# Rov3_-_zasilanie_silniki_v4.net
KiCad netlist of a schematic drawn in EAGLE
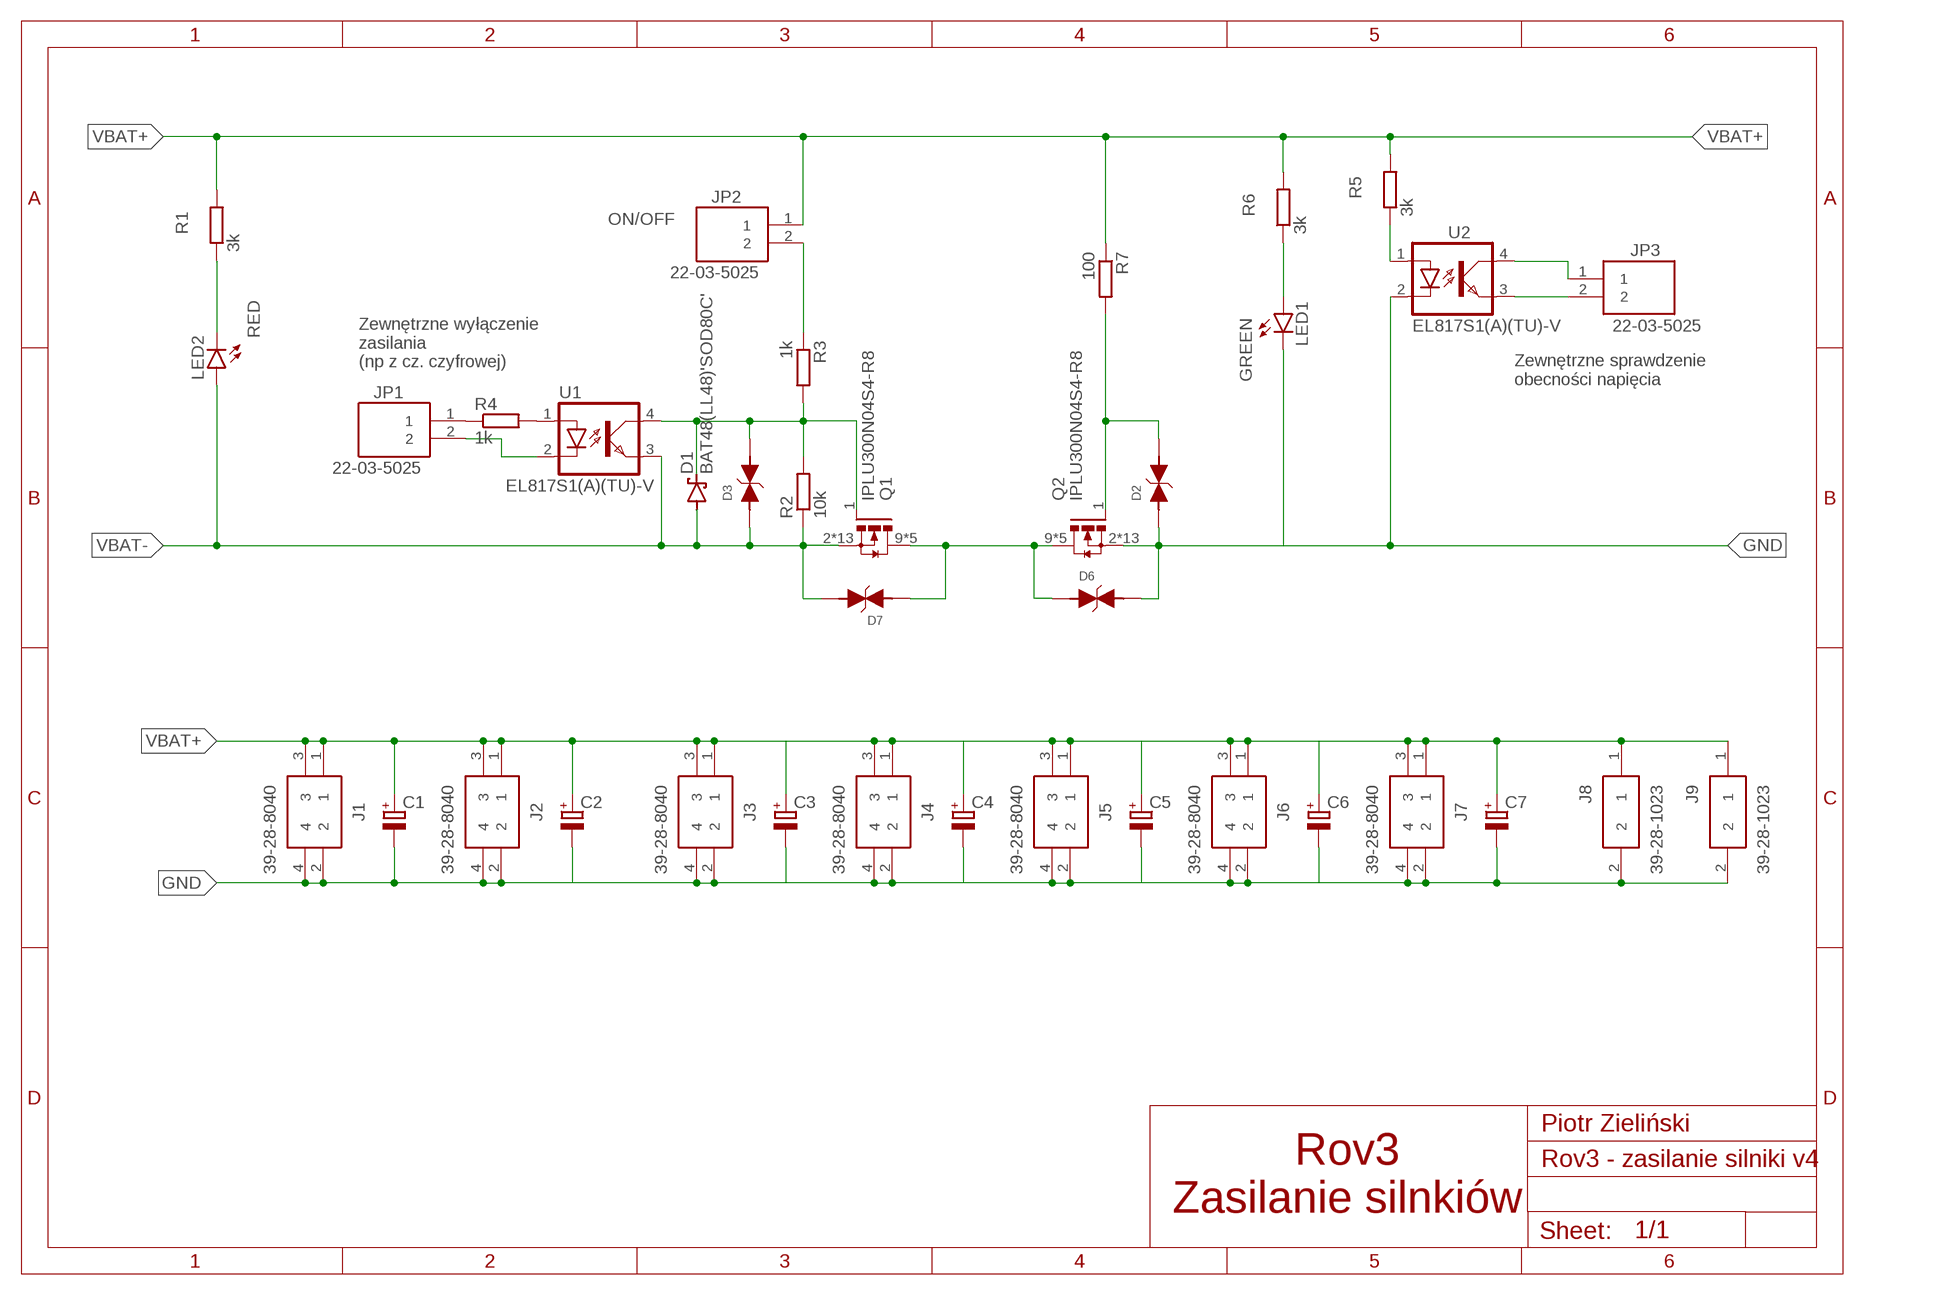
[diagram p0: schematic, sheet 1]

(export (version "E")
  (design (tool "Eeschema 10.0.6"))
  (components
    (comp (ref "C1")
      (value "CPOL-EUE5-10.5")
      (footprint "eagle-import:E5-10,5")
      (libsource (lib "eagle-import") (part "CPOL-EUE5-10.5"))
    )
    (comp (ref "C2")
      (value "CPOL-EUE5-10.5")
      (footprint "eagle-import:E5-10,5")
      (libsource (lib "eagle-import") (part "CPOL-EUE5-10.5"))
    )
    (comp (ref "C3")
      (value "CPOL-EUE5-10.5")
      (footprint "eagle-import:E5-10,5")
      (libsource (lib "eagle-import") (part "CPOL-EUE5-10.5"))
    )
    (comp (ref "C4")
      (value "CPOL-EUE5-10.5")
      (footprint "eagle-import:E5-10,5")
      (libsource (lib "eagle-import") (part "CPOL-EUE5-10.5"))
    )
    (comp (ref "C5")
      (value "CPOL-EUE5-10.5")
      (footprint "eagle-import:E5-10,5")
      (libsource (lib "eagle-import") (part "CPOL-EUE5-10.5"))
    )
    (comp (ref "C6")
      (value "CPOL-EUE5-10.5")
      (footprint "eagle-import:E5-10,5")
      (libsource (lib "eagle-import") (part "CPOL-EUE5-10.5"))
    )
    (comp (ref "C7")
      (value "CPOL-EUE5-10.5")
      (footprint "eagle-import:E5-10,5")
      (libsource (lib "eagle-import") (part "CPOL-EUE5-10.5"))
    )
    (comp (ref "D1")
      (value "BAT48(LL48)'SOD80C'")
      (footprint "eagle-import:SOD80C")
      (libsource (lib "eagle-import") (part "BAT48(LL48)'SOD80C'"))
    )
    (comp (ref "D2")
      (value "P6SMB20A_824501101")
      (footprint "eagle-import:VARTVSP_SMA_DO-214AC")
      (libsource (lib "eagle-import") (part "P6SMB20A_824501101"))
    )
    (comp (ref "D3")
      (value "P6SMB20A_824501101")
      (footprint "eagle-import:VARTVSP_SMA_DO-214AC")
      (libsource (lib "eagle-import") (part "P6SMB20A_824501101"))
    )
    (comp (ref "D6")
      (value "P6SMB20A_824501101")
      (footprint "eagle-import:VARTVSP_SMA_DO-214AC")
      (libsource (lib "eagle-import") (part "P6SMB20A_824501101"))
    )
    (comp (ref "D7")
      (value "P6SMB20A_824501101")
      (footprint "eagle-import:VARTVSP_SMA_DO-214AC")
      (libsource (lib "eagle-import") (part "P6SMB20A_824501101"))
    )
    (comp (ref "J1")
      (value "39-28-8040")
      (footprint "eagle-import:MOLEX_2X2_PCB_SOCKET")
      (fields (field (name "MOUSER_PART_NUMBER") "538-39-28-8040"))
      (libsource (lib "eagle-import") (part "39-28-8040"))
    )
    (comp (ref "J2")
      (value "39-28-8040")
      (footprint "eagle-import:MOLEX_2X2_PCB_SOCKET")
      (fields (field (name "MOUSER_PART_NUMBER") "538-39-28-8040"))
      (libsource (lib "eagle-import") (part "39-28-8040"))
    )
    (comp (ref "J3")
      (value "39-28-8040")
      (footprint "eagle-import:MOLEX_2X2_PCB_SOCKET")
      (fields (field (name "MOUSER_PART_NUMBER") "538-39-28-8040"))
      (libsource (lib "eagle-import") (part "39-28-8040"))
    )
    (comp (ref "J4")
      (value "39-28-8040")
      (footprint "eagle-import:MOLEX_2X2_PCB_SOCKET")
      (fields (field (name "MOUSER_PART_NUMBER") "538-39-28-8040"))
      (libsource (lib "eagle-import") (part "39-28-8040"))
    )
    (comp (ref "J5")
      (value "39-28-8040")
      (footprint "eagle-import:MOLEX_2X2_PCB_SOCKET")
      (fields (field (name "MOUSER_PART_NUMBER") "538-39-28-8040"))
      (libsource (lib "eagle-import") (part "39-28-8040"))
    )
    (comp (ref "J6")
      (value "39-28-8040")
      (footprint "eagle-import:MOLEX_2X2_PCB_SOCKET")
      (fields (field (name "MOUSER_PART_NUMBER") "538-39-28-8040"))
      (libsource (lib "eagle-import") (part "39-28-8040"))
    )
    (comp (ref "J7")
      (value "39-28-8040")
      (footprint "eagle-import:MOLEX_2X2_PCB_SOCKET")
      (fields (field (name "MOUSER_PART_NUMBER") "538-39-28-8040"))
      (libsource (lib "eagle-import") (part "39-28-8040"))
    )
    (comp (ref "J8")
      (value "39-28-1023")
      (footprint "eagle-import:MOLEX_1X2_PCB_SOCKET")
      (fields (field (name "MOUSER_PART_NUMBER") "538-39-28-1023"))
      (libsource (lib "eagle-import") (part "39-28-1023"))
    )
    (comp (ref "J9")
      (value "39-28-1023")
      (footprint "eagle-import:MOLEX_1X2_PCB_SOCKET")
      (fields (field (name "MOUSER_PART_NUMBER") "538-39-28-1023"))
      (libsource (lib "eagle-import") (part "39-28-1023"))
    )
    (comp (ref "JP1")
      (value "22-03-5025")
      (footprint "eagle-import:2.50MM_MINI-SPOX_2PIN_PCB_SOCKET")
      (fields (field (name "MOUSER_PART_NUMBER") "538-22-03-5025"))
      (libsource (lib "eagle-import") (part "22-03-5025"))
    )
    (comp (ref "JP2")
      (value "22-03-5025")
      (footprint "eagle-import:2.50MM_MINI-SPOX_2PIN_PCB_SOCKET")
      (fields (field (name "MOUSER_PART_NUMBER") "538-22-03-5025"))
      (libsource (lib "eagle-import") (part "22-03-5025"))
    )
    (comp (ref "JP3")
      (value "22-03-5025")
      (footprint "eagle-import:2.50MM_MINI-SPOX_2PIN_PCB_SOCKET")
      (fields (field (name "MOUSER_PART_NUMBER") "538-22-03-5025"))
      (libsource (lib "eagle-import") (part "22-03-5025"))
    )
    (comp (ref "LED1")
      (value "GREEN")
      (footprint "eagle-import:CHIP-LED0805")
      (libsource (lib "eagle-import") (part "LEDCHIP-LED0805"))
    )
    (comp (ref "LED2")
      (value "RED")
      (footprint "eagle-import:CHIP-LED0805")
      (libsource (lib "eagle-import") (part "LEDCHIP-LED0805"))
    )
    (comp (ref "Q1")
      (value "IPLU300N04S4-R8")
      (footprint "eagle-import:PG-HSOF-8-1")
      (fields (field (name "MOUSER_PART_NUMBER") "726-IPLU300N04S4-R8"))
      (libsource (lib "eagle-import") (part "IPLU300N04S4-R8"))
    )
    (comp (ref "Q2")
      (value "IPLU300N04S4-R8")
      (footprint "eagle-import:PG-HSOF-8-1")
      (fields (field (name "MOUSER_PART_NUMBER") "726-IPLU300N04S4-R8"))
      (libsource (lib "eagle-import") (part "IPLU300N04S4-R8"))
    )
    (comp (ref "R1")
      (value "3k")
      (footprint "eagle-import:R1206")
      (libsource (lib "eagle-import") (part "R-EU_R1206"))
    )
    (comp (ref "R2")
      (value "10k")
      (footprint "eagle-import:R1206")
      (libsource (lib "eagle-import") (part "R-EU_R1206"))
    )
    (comp (ref "R3")
      (value "1k")
      (footprint "eagle-import:R1206")
      (libsource (lib "eagle-import") (part "R-EU_R1206"))
    )
    (comp (ref "R4")
      (value "1k")
      (footprint "eagle-import:R1206")
      (libsource (lib "eagle-import") (part "R-EU_R1206"))
    )
    (comp (ref "R5")
      (value "3k")
      (footprint "eagle-import:R1206")
      (libsource (lib "eagle-import") (part "R-EU_R1206"))
    )
    (comp (ref "R6")
      (value "3k")
      (footprint "eagle-import:R1206")
      (libsource (lib "eagle-import") (part "R-EU_R1206"))
    )
    (comp (ref "R7")
      (value "100")
      (footprint "eagle-import:R1206")
      (libsource (lib "eagle-import") (part "R-EU_R1206"))
    )
    (comp (ref "U1")
      (value "EL817S1(A)(TU)-V")
      (footprint "eagle-import:SOIC254P1030X390-4N_EL817S1(A)(TU)-V")
      (fields (field (name "MF") "Everlight Electronics") (field (name "MP") "EL817S1_A__TU_-V"))
      (libsource (lib "eagle-import") (part "EL817S1(A)(TU)-V"))
    )
    (comp (ref "U2")
      (value "EL817S1(A)(TU)-V")
      (footprint "eagle-import:SOIC254P1030X390-4N_EL817S1(A)(TU)-V")
      (fields (field (name "MF") "Everlight Electronics") (field (name "MP") "EL817S1_A__TU_-V"))
      (libsource (lib "eagle-import") (part "EL817S1(A)(TU)-V"))
    )
  )
  (nets
    (net (code "1") (name "GND") (class "Default")
      (node (ref "C1") (pin "-") (pinfunction "-_-") (pintype "passive"))
      (node (ref "C2") (pin "-") (pinfunction "-_-") (pintype "passive"))
      (node (ref "C3") (pin "-") (pinfunction "-_-") (pintype "passive"))
      (node (ref "C4") (pin "-") (pinfunction "-_-") (pintype "passive"))
      (node (ref "C5") (pin "-") (pinfunction "-_-") (pintype "passive"))
      (node (ref "C6") (pin "-") (pinfunction "-_-") (pintype "passive"))
      (node (ref "C7") (pin "-") (pinfunction "-_-") (pintype "passive"))
      (node (ref "D2") (pin "1") (pinfunction "1_1") (pintype "passive"))
      (node (ref "D6") (pin "2") (pinfunction "2_2") (pintype "passive"))
      (node (ref "J1") (pin "2") (pinfunction "2_2") (pintype "bidirectional"))
      (node (ref "J1") (pin "4") (pinfunction "4_4") (pintype "bidirectional"))
      (node (ref "J2") (pin "2") (pinfunction "2_2") (pintype "bidirectional"))
      (node (ref "J2") (pin "4") (pinfunction "4_4") (pintype "bidirectional"))
      (node (ref "J3") (pin "2") (pinfunction "2_2") (pintype "bidirectional"))
      (node (ref "J3") (pin "4") (pinfunction "4_4") (pintype "bidirectional"))
      (node (ref "J4") (pin "2") (pinfunction "2_2") (pintype "bidirectional"))
      (node (ref "J4") (pin "4") (pinfunction "4_4") (pintype "bidirectional"))
      (node (ref "J5") (pin "2") (pinfunction "2_2") (pintype "bidirectional"))
      (node (ref "J5") (pin "4") (pinfunction "4_4") (pintype "bidirectional"))
      (node (ref "J6") (pin "2") (pinfunction "2_2") (pintype "bidirectional"))
      (node (ref "J6") (pin "4") (pinfunction "4_4") (pintype "bidirectional"))
      (node (ref "J7") (pin "2") (pinfunction "2_2") (pintype "bidirectional"))
      (node (ref "J7") (pin "4") (pinfunction "4_4") (pintype "bidirectional"))
      (node (ref "J8") (pin "2") (pinfunction "2_2") (pintype "bidirectional"))
      (node (ref "J9") (pin "2") (pinfunction "2_2") (pintype "bidirectional"))
      (node (ref "LED1") (pin "C") (pinfunction "C_C") (pintype "passive"))
      (node (ref "Q2") (pin "10") (pinfunction "S_10") (pintype "passive"))
      (node (ref "Q2") (pin "11") (pinfunction "S_11") (pintype "passive"))
      (node (ref "Q2") (pin "12") (pinfunction "S_12") (pintype "passive"))
      (node (ref "Q2") (pin "13") (pinfunction "S_13") (pintype "passive"))
      (node (ref "Q2") (pin "14") (pinfunction "S_14") (pintype "passive"))
      (node (ref "Q2") (pin "15") (pinfunction "S_15") (pintype "passive"))
      (node (ref "Q2") (pin "2") (pinfunction "S_2") (pintype "passive"))
      (node (ref "Q2") (pin "3") (pinfunction "S_3") (pintype "passive"))
      (node (ref "Q2") (pin "4") (pinfunction "S_4") (pintype "passive"))
      (node (ref "Q2") (pin "5") (pinfunction "S_5") (pintype "passive"))
      (node (ref "Q2") (pin "6") (pinfunction "S_6") (pintype "passive"))
      (node (ref "Q2") (pin "7") (pinfunction "S_7") (pintype "passive"))
      (node (ref "Q2") (pin "8") (pinfunction "S_8") (pintype "passive"))
      (node (ref "U2") (pin "2") (pinfunction "C_2") (pintype "passive"))
    )
    (net (code "2") (name "Net-(D6-Pad1)") (class "Default")
      (node (ref "D6") (pin "1") (pinfunction "1_1") (pintype "passive"))
      (node (ref "D7") (pin "1") (pinfunction "1_1") (pintype "passive"))
      (node (ref "Q1") (pin "16") (pinfunction "D_16") (pintype "passive"))
      (node (ref "Q1") (pin "17") (pinfunction "D_17") (pintype "passive"))
      (node (ref "Q1") (pin "18") (pinfunction "D_18") (pintype "passive"))
      (node (ref "Q1") (pin "19") (pinfunction "D_19") (pintype "passive"))
      (node (ref "Q1") (pin "9") (pinfunction "D_9") (pintype "passive"))
      (node (ref "Q2") (pin "16") (pinfunction "D_16") (pintype "passive"))
      (node (ref "Q2") (pin "17") (pinfunction "D_17") (pintype "passive"))
      (node (ref "Q2") (pin "18") (pinfunction "D_18") (pintype "passive"))
      (node (ref "Q2") (pin "19") (pinfunction "D_19") (pintype "passive"))
      (node (ref "Q2") (pin "9") (pinfunction "D_9") (pintype "passive"))
    )
    (net (code "3") (name "Net-(JP1-Pad1)") (class "Default")
      (node (ref "JP1") (pin "1") (pinfunction "1_1") (pintype "bidirectional"))
      (node (ref "R4") (pin "1") (pinfunction "1_1") (pintype "passive"))
    )
    (net (code "4") (name "Net-(JP2-Pad2)") (class "Default")
      (node (ref "JP2") (pin "2") (pinfunction "2_2") (pintype "bidirectional"))
      (node (ref "R3") (pin "1") (pinfunction "1_1") (pintype "passive"))
    )
    (net (code "5") (name "Net-(LED1-PadA)") (class "Default")
      (node (ref "LED1") (pin "A") (pinfunction "A_A") (pintype "passive"))
      (node (ref "R6") (pin "1") (pinfunction "1_1") (pintype "passive"))
    )
    (net (code "6") (name "Net-(LED2-PadC)") (class "Default")
      (node (ref "LED2") (pin "C") (pinfunction "C_C") (pintype "passive"))
      (node (ref "R1") (pin "1") (pinfunction "1_1") (pintype "passive"))
    )
    (net (code "7") (name "Net-(Q1-G)") (class "Default")
      (node (ref "D1") (pin "C") (pinfunction "C_C") (pintype "passive"))
      (node (ref "D3") (pin "2") (pinfunction "2_2") (pintype "passive"))
      (node (ref "Q1") (pin "1") (pinfunction "G_1") (pintype "passive"))
      (node (ref "R2") (pin "2") (pinfunction "2_2") (pintype "passive"))
      (node (ref "R3") (pin "2") (pinfunction "2_2") (pintype "passive"))
      (node (ref "U1") (pin "4") (pinfunction "COL_4") (pintype "passive"))
    )
    (net (code "8") (name "Net-(Q2-G)") (class "Default")
      (node (ref "D2") (pin "2") (pinfunction "2_2") (pintype "passive"))
      (node (ref "Q2") (pin "1") (pinfunction "G_1") (pintype "passive"))
      (node (ref "R7") (pin "2") (pinfunction "2_2") (pintype "passive"))
    )
    (net (code "9") (name "Net-(U1-A)") (class "Default")
      (node (ref "R4") (pin "2") (pinfunction "2_2") (pintype "passive"))
      (node (ref "U1") (pin "1") (pinfunction "A_1") (pintype "passive"))
    )
    (net (code "10") (name "Net-(U1-C)") (class "Default")
      (node (ref "JP1") (pin "2") (pinfunction "2_2") (pintype "bidirectional"))
      (node (ref "U1") (pin "2") (pinfunction "C_2") (pintype "passive"))
    )
    (net (code "11") (name "Net-(U2-A)") (class "Default")
      (node (ref "R5") (pin "1") (pinfunction "1_1") (pintype "passive"))
      (node (ref "U2") (pin "1") (pinfunction "A_1") (pintype "passive"))
    )
    (net (code "12") (name "Net-(U2-COL)") (class "Default")
      (node (ref "JP3") (pin "1") (pinfunction "1_1") (pintype "bidirectional"))
      (node (ref "U2") (pin "4") (pinfunction "COL_4") (pintype "passive"))
    )
    (net (code "13") (name "Net-(U2-EMIT)") (class "Default")
      (node (ref "JP3") (pin "2") (pinfunction "2_2") (pintype "bidirectional"))
      (node (ref "U2") (pin "3") (pinfunction "EMIT_3") (pintype "passive"))
    )
    (net (code "14") (name "VBAT+") (class "Default")
      (node (ref "C1") (pin "+") (pinfunction "+_+") (pintype "passive"))
      (node (ref "C2") (pin "+") (pinfunction "+_+") (pintype "passive"))
      (node (ref "C3") (pin "+") (pinfunction "+_+") (pintype "passive"))
      (node (ref "C4") (pin "+") (pinfunction "+_+") (pintype "passive"))
      (node (ref "C5") (pin "+") (pinfunction "+_+") (pintype "passive"))
      (node (ref "C6") (pin "+") (pinfunction "+_+") (pintype "passive"))
      (node (ref "C7") (pin "+") (pinfunction "+_+") (pintype "passive"))
      (node (ref "J1") (pin "1") (pinfunction "1_1") (pintype "bidirectional"))
      (node (ref "J1") (pin "3") (pinfunction "3_3") (pintype "bidirectional"))
      (node (ref "J2") (pin "1") (pinfunction "1_1") (pintype "bidirectional"))
      (node (ref "J2") (pin "3") (pinfunction "3_3") (pintype "bidirectional"))
      (node (ref "J3") (pin "1") (pinfunction "1_1") (pintype "bidirectional"))
      (node (ref "J3") (pin "3") (pinfunction "3_3") (pintype "bidirectional"))
      (node (ref "J4") (pin "1") (pinfunction "1_1") (pintype "bidirectional"))
      (node (ref "J4") (pin "3") (pinfunction "3_3") (pintype "bidirectional"))
      (node (ref "J5") (pin "1") (pinfunction "1_1") (pintype "bidirectional"))
      (node (ref "J5") (pin "3") (pinfunction "3_3") (pintype "bidirectional"))
      (node (ref "J6") (pin "1") (pinfunction "1_1") (pintype "bidirectional"))
      (node (ref "J6") (pin "3") (pinfunction "3_3") (pintype "bidirectional"))
      (node (ref "J7") (pin "1") (pinfunction "1_1") (pintype "bidirectional"))
      (node (ref "J7") (pin "3") (pinfunction "3_3") (pintype "bidirectional"))
      (node (ref "J8") (pin "1") (pinfunction "1_1") (pintype "bidirectional"))
      (node (ref "J9") (pin "1") (pinfunction "1_1") (pintype "bidirectional"))
      (node (ref "JP2") (pin "1") (pinfunction "1_1") (pintype "bidirectional"))
      (node (ref "R1") (pin "2") (pinfunction "2_2") (pintype "passive"))
      (node (ref "R5") (pin "2") (pinfunction "2_2") (pintype "passive"))
      (node (ref "R6") (pin "2") (pinfunction "2_2") (pintype "passive"))
      (node (ref "R7") (pin "1") (pinfunction "1_1") (pintype "passive"))
    )
    (net (code "15") (name "VBAT-") (class "Default")
      (node (ref "D1") (pin "A") (pinfunction "A_A") (pintype "passive"))
      (node (ref "D3") (pin "1") (pinfunction "1_1") (pintype "passive"))
      (node (ref "D7") (pin "2") (pinfunction "2_2") (pintype "passive"))
      (node (ref "LED2") (pin "A") (pinfunction "A_A") (pintype "passive"))
      (node (ref "Q1") (pin "10") (pinfunction "S_10") (pintype "passive"))
      (node (ref "Q1") (pin "11") (pinfunction "S_11") (pintype "passive"))
      (node (ref "Q1") (pin "12") (pinfunction "S_12") (pintype "passive"))
      (node (ref "Q1") (pin "13") (pinfunction "S_13") (pintype "passive"))
      (node (ref "Q1") (pin "14") (pinfunction "S_14") (pintype "passive"))
      (node (ref "Q1") (pin "15") (pinfunction "S_15") (pintype "passive"))
      (node (ref "Q1") (pin "2") (pinfunction "S_2") (pintype "passive"))
      (node (ref "Q1") (pin "3") (pinfunction "S_3") (pintype "passive"))
      (node (ref "Q1") (pin "4") (pinfunction "S_4") (pintype "passive"))
      (node (ref "Q1") (pin "5") (pinfunction "S_5") (pintype "passive"))
      (node (ref "Q1") (pin "6") (pinfunction "S_6") (pintype "passive"))
      (node (ref "Q1") (pin "7") (pinfunction "S_7") (pintype "passive"))
      (node (ref "Q1") (pin "8") (pinfunction "S_8") (pintype "passive"))
      (node (ref "R2") (pin "1") (pinfunction "1_1") (pintype "passive"))
      (node (ref "U1") (pin "3") (pinfunction "EMIT_3") (pintype "passive"))
    )
  )
)
